# amplifier.net
KiCad netlist of a schematic drawn in Altium Designer
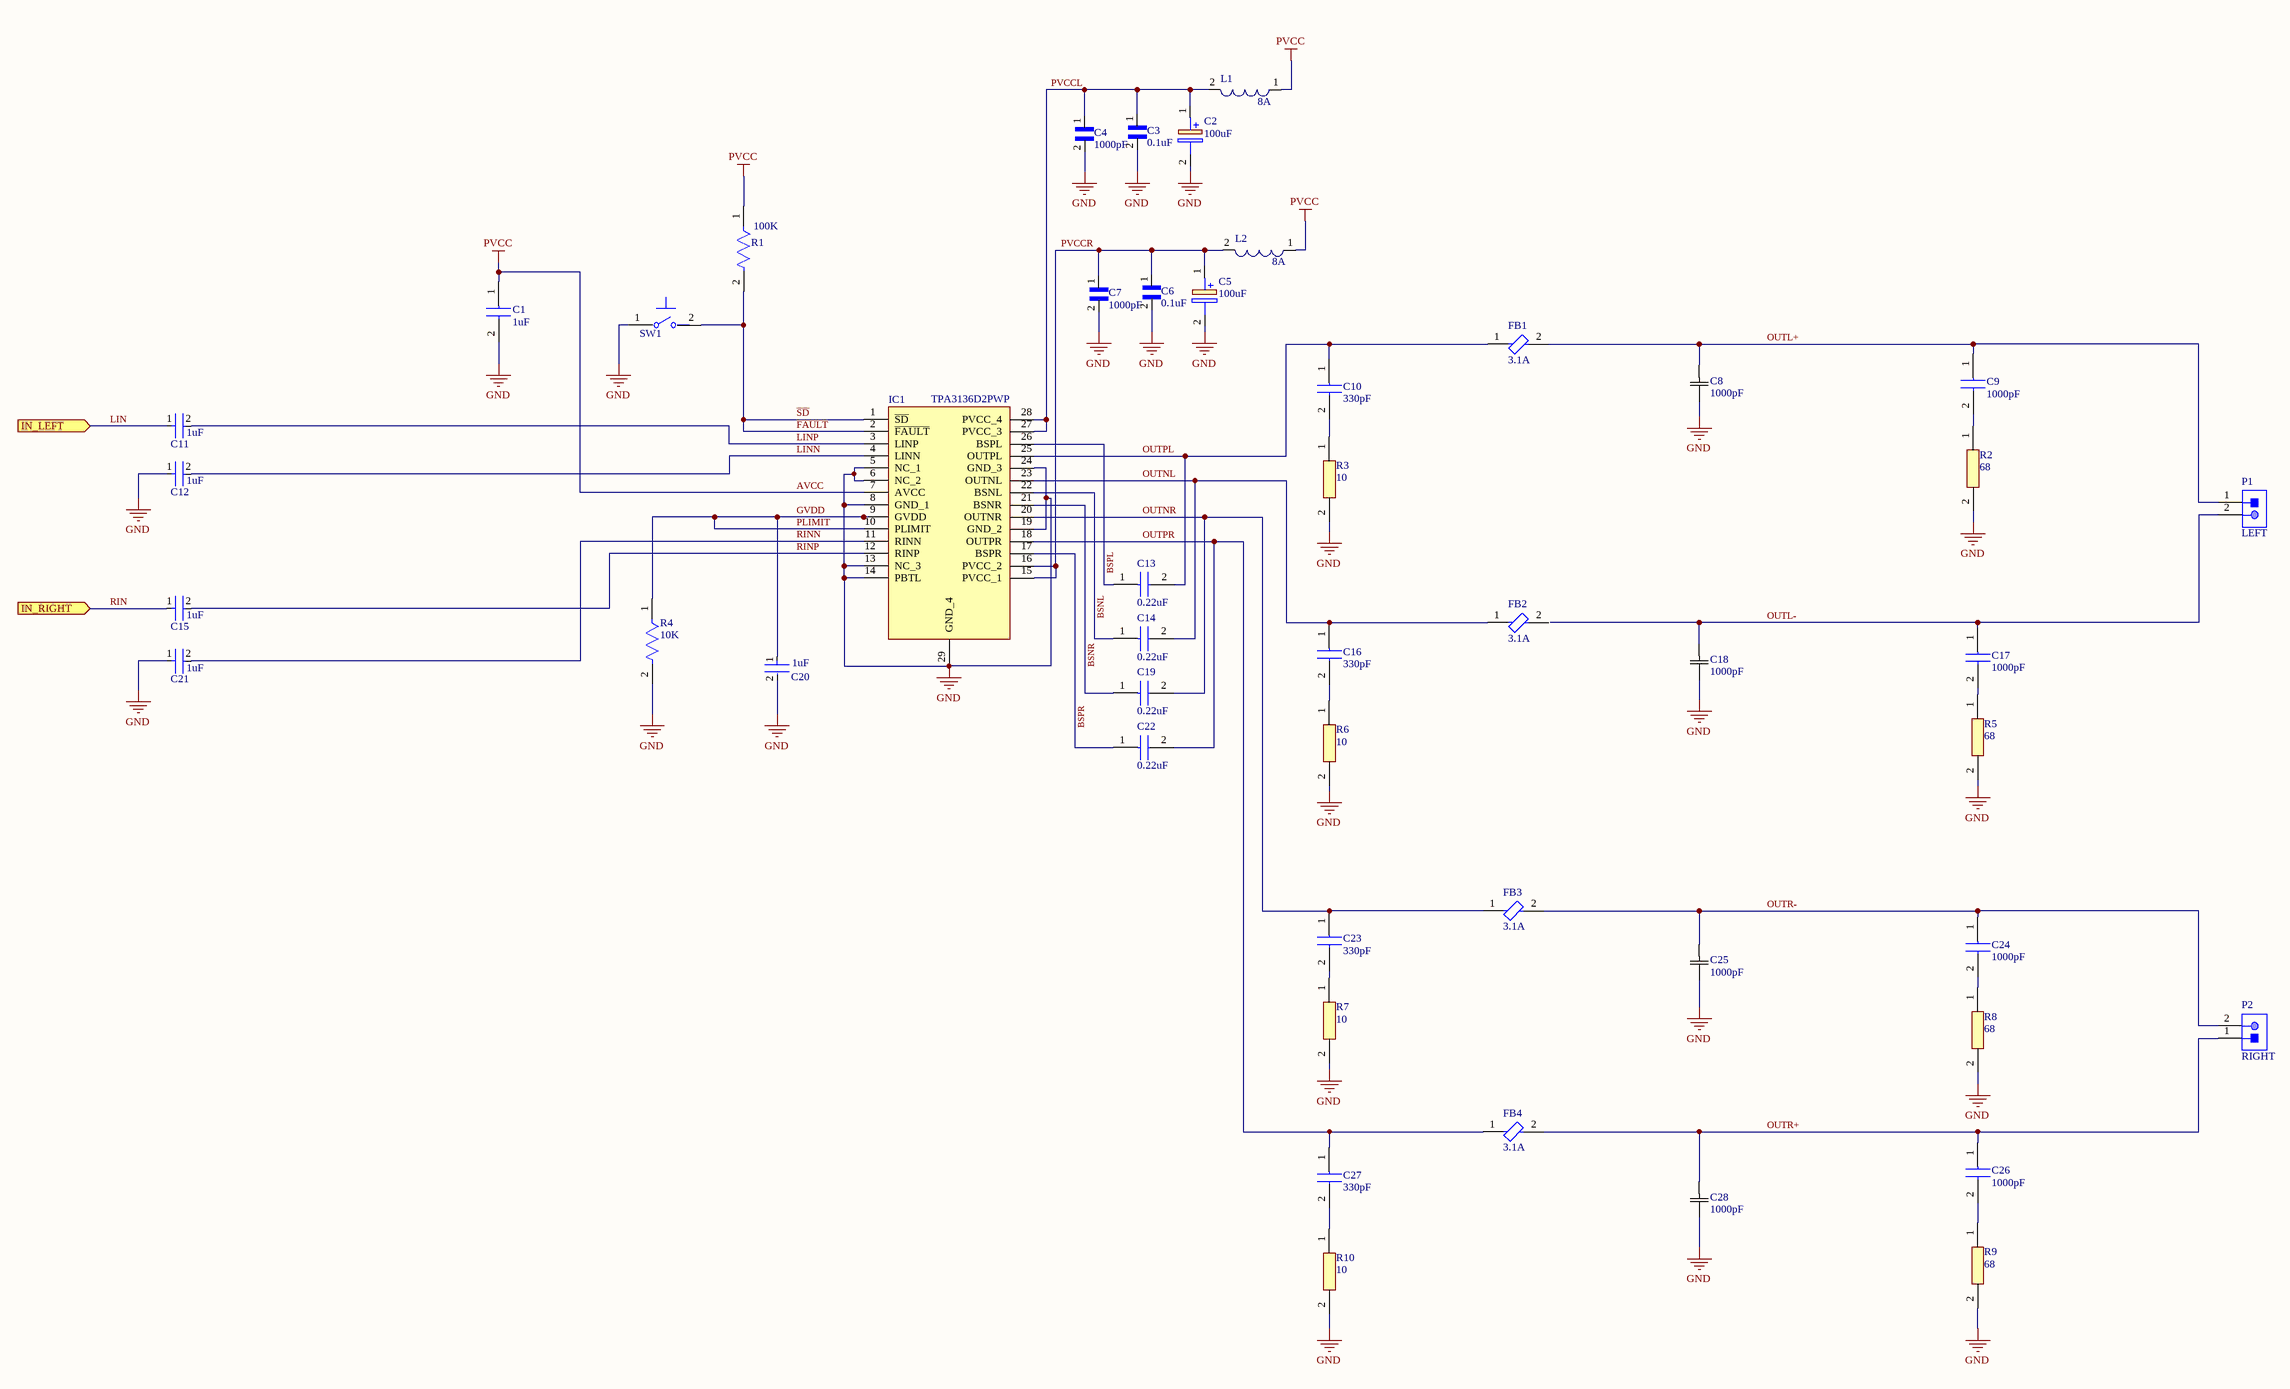
[diagram p0: amplifier.SchDoc]

(export (version "E")
  (design (tool "Eeschema 10.0.6"))
  (components
    (comp (ref "C1")
      (value "1uF")
      (footprint "CAPC1608X90N")
      (description "CAP CER 1UF 35V X5R 0603")
      (fields
        (field (name "MANUFACTURER_PART_NUMBER") "GMK107BJ105KA-T")
        (field (name "MOUSER PART NUMBER") "963-GMK107BJ105KA-T")
      )
      (libsource (lib "project_x_sch_library") (part "GMK107BJ105KA-T"))
    )
    (comp (ref "C2")
      (value "100uF")
      (footprint "CAPPRD350W60D825H1300")
      (description "CAP ALUM 100UF 20% 50V RADIAL")
      (fields
        (field (name "MANUFACTURER_PART_NUMBER") "UHE1H101MPD")
        (field (name "MOUSER PART NUMBER") "647-UHE1H101MPD")
      )
      (libsource (lib "project_x_sch_library") (part "UHE1H101MPD"))
    )
    (comp (ref "C3")
      (value "0.1uF")
      (footprint "CAPC1608X90N")
      (description "CAP CER 0.1UF 50V X7R 0603")
      (fields (field (name "MP") "CL10B104KB8NNNL") (field (name "MF") "Samsung Electro-Mechanics"))
      (libsource (lib "project_x_sch_library") (part "CL10B104KB8NNNL"))
    )
    (comp (ref "C4")
      (value "1000pF")
      (footprint "CAPC1608X90N")
      (description "1000pF ±5% 50V Ceramic Capacitor C0G, NP0 0603 (1608 Metric)")
      (fields (field (name "MP") "06035A102JAT2A"))
      (libsource (lib "project_x_sch_library") (part "06035A102JAT2A"))
    )
    (comp (ref "C5")
      (value "100uF")
      (footprint "CAPPRD350W60D825H1300")
      (description "CAP ALUM 100UF 20% 50V RADIAL")
      (fields
        (field (name "MANUFACTURER_PART_NUMBER") "UHE1H101MPD")
        (field (name "MOUSER PART NUMBER") "647-UHE1H101MPD")
      )
      (libsource (lib "project_x_sch_library") (part "UHE1H101MPD"))
    )
    (comp (ref "C6")
      (value "0.1uF")
      (footprint "CAPC1608X90N")
      (description "CAP CER 0.1UF 50V X7R 0603")
      (fields (field (name "MP") "CL10B104KB8NNNL") (field (name "MF") "Samsung Electro-Mechanics"))
      (libsource (lib "project_x_sch_library") (part "CL10B104KB8NNNL"))
    )
    (comp (ref "C7")
      (value "1000pF")
      (footprint "CAPC1608X90N")
      (description "1000pF ±5% 50V Ceramic Capacitor C0G, NP0 0603 (1608 Metric)")
      (fields (field (name "MP") "06035A102JAT2A"))
      (libsource (lib "project_x_sch_library") (part "06035A102JAT2A"))
    )
    (comp (ref "C8")
      (value "1000pF")
      (footprint "CAPC3216X94N")
      (description "CAP CER 1000PF 100V X7R 1206")
      (fields
        (field (name "MANUFACTURER_PART_NUMBER") "12061C102KAT2A")
        (field (name "COPYRIGHT") "Copyright (C) 2018 Accelerated Designs. All rights reserved")
      )
      (libsource (lib "project_x_sch_library") (part "12061C102KAT2A"))
    )
    (comp (ref "C9")
      (value "1000pF")
      (footprint "CAPC1608X90N")
      (description "CAP CER 1000PF 50V C0G/NP0 0603")
      (fields
        (field (name "MANUFACTURER_PART_NUMBER") "06035A102KAT2A")
        (field (name "MOUSER PART NUMBER") "581-06035A102KAT2A")
      )
      (libsource (lib "project_x_sch_library") (part "06035A102KAT2A"))
    )
    (comp (ref "C10")
      (value "330pF")
      (footprint "CAPC1608X90N")
      (description "CAP CER 330PF 50V C0G/NP0 0603")
      (fields
        (field (name "MANUFACTURER_PART_NUMBER") "06035A331JAT2A")
        (field (name "MOUSER PART NUMBER") "581-06035A331J")
      )
      (libsource (lib "project_x_sch_library") (part "06035A331JAT2A"))
    )
    (comp (ref "C11")
      (value "1uF")
      (footprint "TDK_CGA3E-0_3-0_1_IPC_A")
      (description "1µF ±10% 16V Ceramic Capacitor X7R 0603 (1608 Metric)")
      (libsource (lib "project_x_sch_library") (part "CGA3E1X7R1C105K080AC"))
    )
    (comp (ref "C12")
      (value "1uF")
      (footprint "TDK_CGA3E-0_3-0_1_IPC_A")
      (description "1µF ±10% 16V Ceramic Capacitor X7R 0603 (1608 Metric)")
      (libsource (lib "project_x_sch_library") (part "CGA3E1X7R1C105K080AC"))
    )
    (comp (ref "C13")
      (value "0.22uF")
      (footprint "CAPC1608X90N")
      (description "CAP CER 0.22UF 25V X5R 0603")
      (fields
        (field (name "MANUFACTURER_PART_NUMBER") "06033D224KAT2A")
        (field (name "MOUSER PART NUMBER") "581-06033D224K")
      )
      (libsource (lib "project_x_sch_library") (part "06033D224KAT2A"))
    )
    (comp (ref "C14")
      (value "0.22uF")
      (footprint "CAPC1608X90N")
      (description "CAP CER 0.22UF 25V X5R 0603")
      (fields
        (field (name "MANUFACTURER_PART_NUMBER") "06033D224KAT2A")
        (field (name "MOUSER PART NUMBER") "581-06033D224K")
      )
      (libsource (lib "project_x_sch_library") (part "06033D224KAT2A"))
    )
    (comp (ref "C15")
      (value "1uF")
      (footprint "TDK_CGA3E-0_3-0_1_IPC_A")
      (description "1µF ±10% 16V Ceramic Capacitor X7R 0603 (1608 Metric)")
      (libsource (lib "project_x_sch_library") (part "CGA3E1X7R1C105K080AC"))
    )
    (comp (ref "C16")
      (value "330pF")
      (footprint "CAPC1608X90N")
      (description "CAP CER 330PF 50V C0G/NP0 0603")
      (fields
        (field (name "MANUFACTURER_PART_NUMBER") "06035A331JAT2A")
        (field (name "MOUSER PART NUMBER") "581-06035A331J")
      )
      (libsource (lib "project_x_sch_library") (part "06035A331JAT2A"))
    )
    (comp (ref "C17")
      (value "1000pF")
      (footprint "CAPC1608X90N")
      (description "CAP CER 1000PF 50V C0G/NP0 0603")
      (fields
        (field (name "MANUFACTURER_PART_NUMBER") "06035A102KAT2A")
        (field (name "MOUSER PART NUMBER") "581-06035A102KAT2A")
      )
      (libsource (lib "project_x_sch_library") (part "06035A102KAT2A"))
    )
    (comp (ref "C18")
      (value "1000pF")
      (footprint "CAPC3216X94N")
      (description "CAP CER 1000PF 100V X7R 1206")
      (fields
        (field (name "MANUFACTURER_PART_NUMBER") "12061C102KAT2A")
        (field (name "COPYRIGHT") "Copyright (C) 2018 Accelerated Designs. All rights reserved")
      )
      (libsource (lib "project_x_sch_library") (part "12061C102KAT2A"))
    )
    (comp (ref "C19")
      (value "0.22uF")
      (footprint "CAPC1608X90N")
      (description "CAP CER 0.22UF 25V X5R 0603")
      (fields
        (field (name "MANUFACTURER_PART_NUMBER") "06033D224KAT2A")
        (field (name "MOUSER PART NUMBER") "581-06033D224K")
      )
      (libsource (lib "project_x_sch_library") (part "06033D224KAT2A"))
    )
    (comp (ref "C20")
      (value "1uF")
      (footprint "TDK_CGA3E-0_3-0_1_IPC_A")
      (description "1µF ±10% 16V Ceramic Capacitor X7R 0603 (1608 Metric)")
      (libsource (lib "project_x_sch_library") (part "CGA3E1X7R1C105K080AC"))
    )
    (comp (ref "C21")
      (value "1uF")
      (footprint "TDK_CGA3E-0_3-0_1_IPC_A")
      (description "1µF ±10% 16V Ceramic Capacitor X7R 0603 (1608 Metric)")
      (libsource (lib "project_x_sch_library") (part "CGA3E1X7R1C105K080AC"))
    )
    (comp (ref "C22")
      (value "0.22uF")
      (footprint "CAPC1608X90N")
      (description "CAP CER 0.22UF 25V X5R 0603")
      (fields
        (field (name "MANUFACTURER_PART_NUMBER") "06033D224KAT2A")
        (field (name "MOUSER PART NUMBER") "581-06033D224K")
      )
      (libsource (lib "project_x_sch_library") (part "06033D224KAT2A"))
    )
    (comp (ref "C23")
      (value "330pF")
      (footprint "CAPC1608X90N")
      (description "CAP CER 330PF 50V C0G/NP0 0603")
      (fields
        (field (name "MANUFACTURER_PART_NUMBER") "06035A331JAT2A")
        (field (name "MOUSER PART NUMBER") "581-06035A331J")
      )
      (libsource (lib "project_x_sch_library") (part "06035A331JAT2A"))
    )
    (comp (ref "C24")
      (value "1000pF")
      (footprint "CAPC1608X90N")
      (description "CAP CER 1000PF 50V C0G/NP0 0603")
      (fields
        (field (name "MANUFACTURER_PART_NUMBER") "06035A102KAT2A")
        (field (name "MOUSER PART NUMBER") "581-06035A102KAT2A")
      )
      (libsource (lib "project_x_sch_library") (part "06035A102KAT2A"))
    )
    (comp (ref "C25")
      (value "1000pF")
      (footprint "CAPC3216X94N")
      (description "CAP CER 1000PF 100V X7R 1206")
      (fields
        (field (name "MANUFACTURER_PART_NUMBER") "12061C102KAT2A")
        (field (name "COPYRIGHT") "Copyright (C) 2018 Accelerated Designs. All rights reserved")
      )
      (libsource (lib "project_x_sch_library") (part "12061C102KAT2A"))
    )
    (comp (ref "C26")
      (value "1000pF")
      (footprint "CAPC1608X90N")
      (description "CAP CER 1000PF 50V C0G/NP0 0603")
      (fields
        (field (name "MANUFACTURER_PART_NUMBER") "06035A102KAT2A")
        (field (name "MOUSER PART NUMBER") "581-06035A102KAT2A")
      )
      (libsource (lib "project_x_sch_library") (part "06035A102KAT2A"))
    )
    (comp (ref "C27")
      (value "330pF")
      (footprint "CAPC1608X90N")
      (description "CAP CER 330PF 50V C0G/NP0 0603")
      (fields
        (field (name "MANUFACTURER_PART_NUMBER") "06035A331JAT2A")
        (field (name "MOUSER PART NUMBER") "581-06035A331J")
      )
      (libsource (lib "project_x_sch_library") (part "06035A331JAT2A"))
    )
    (comp (ref "C28")
      (value "1000pF")
      (footprint "CAPC3216X94N")
      (description "CAP CER 1000PF 100V X7R 1206")
      (fields
        (field (name "MANUFACTURER_PART_NUMBER") "12061C102KAT2A")
        (field (name "COPYRIGHT") "Copyright (C) 2018 Accelerated Designs. All rights reserved")
      )
      (libsource (lib "project_x_sch_library") (part "12061C102KAT2A"))
    )
    (comp (ref "FB1")
      (value "3.1A")
      (footprint "Murata_NFZ2MSD-d5_IPC_A")
      (description "300 Ohms @ 100MHz 1  Ferrite Bead 0806 (2016 Metric) 3.8A 26mOhm")
      (libsource (lib "project_x_sch_library") (part "NFZ2MSD301SZ10L"))
    )
    (comp (ref "FB2")
      (value "3.1A")
      (footprint "Murata_NFZ2MSD-d5_IPC_A")
      (description "300 Ohms @ 100MHz 1  Ferrite Bead 0806 (2016 Metric) 3.8A 26mOhm")
      (libsource (lib "project_x_sch_library") (part "NFZ2MSD301SZ10L"))
    )
    (comp (ref "FB3")
      (value "3.1A")
      (footprint "Murata_NFZ2MSD-d5_IPC_A")
      (description "300 Ohms @ 100MHz 1  Ferrite Bead 0806 (2016 Metric) 3.8A 26mOhm")
      (libsource (lib "project_x_sch_library") (part "NFZ2MSD301SZ10L"))
    )
    (comp (ref "FB4")
      (value "3.1A")
      (footprint "Murata_NFZ2MSD-d5_IPC_A")
      (description "300 Ohms @ 100MHz 1  Ferrite Bead 0806 (2016 Metric) 3.8A 26mOhm")
      (libsource (lib "project_x_sch_library") (part "NFZ2MSD301SZ10L"))
    )
    (comp (ref "IC1")
      (value "TPA3136D2PWP")
      (footprint "SOP65P640X120-29N")
      (description "IC AMP CLASS D STER 10W 28HTSSOP")
      (fields (field (name "MOUSER PART NUMBER") "595-TPA3136D2PWP"))
      (libsource (lib "project_x_sch_library") (part "TPA3136D2PWP"))
    )
    (comp (ref "L1")
      (value "8A")
      (footprint "WE-MPSB-1812")
      (description "100 Ohms @ 100MHz 1  Ferrite Bead 1812 (4532 Metric) 8A 6mOhm")
      (fields (field (name "PARTNUMBER") "74279226101") (field (name "MANUFACTURER") "Wuerth Elektronik"))
      (libsource (lib "project_x_sch_library") (part "74279226101"))
    )
    (comp (ref "L2")
      (value "8A")
      (footprint "WE-MPSB-1812")
      (description "100 Ohms @ 100MHz 1  Ferrite Bead 1812 (4532 Metric) 8A 6mOhm")
      (fields (field (name "PARTNUMBER") "74279226101") (field (name "MANUFACTURER") "Wuerth Elektronik"))
      (libsource (lib "project_x_sch_library") (part "74279226101"))
    )
    (comp (ref "P1")
      (value "LEFT")
      (footprint "PHOE-1803277_V")
      (fields (field (name "TOLERANCE") "5%") (field (name "PARTNUMBER") "1803277"))
      (libsource (lib "") (part "1803277_1"))
    )
    (comp (ref "P2")
      (value "RIGHT")
      (footprint "PHOE-1803277_V")
      (fields (field (name "TOLERANCE") "5%") (field (name "PARTNUMBER") "1803277"))
      (libsource (lib "project_x_sch_library") (part "1803277"))
    )
    (comp (ref "R1")
      (value "100K")
      (footprint "TE_Connectivity_CPF0603_IPC_A")
      (description "100 kOhms ±1% 0.063W, 1/16W Chip Resistor 0603 (1608 Metric)  Thin Film")
      (libsource (lib "project_x_sch_library") (part "CPF0603F100KC1"))
    )
    (comp (ref "R2")
      (value "68")
      (footprint "RESC1608X55N - duplicate")
      (description "RES SMD 68 OHM 5% 1/10W 0603")
      (fields
        (field (name "MANUFACTURER_PART_NUMBER") "RC0603JR-0768RL")
        (field (name "MOUSER PART NUMBER") "603-RC0603JR-0768RL")
      )
      (libsource (lib "project_x_sch_library") (part "RC0603JR-0768RL"))
    )
    (comp (ref "R3")
      (value "10")
      (footprint "RESC1608X55N")
      (description "RES SMD 10 OHM 1% 1/4W 0603")
      (fields
        (field (name "MANUFACTURER_PART_NUMBER") "ESR03EZPF10R0")
        (field (name "MOUSER PART NUMBER") "755-ESR03EZPF10R0")
      )
      (libsource (lib "project_x_sch_library") (part "ESR03EZPF10R0"))
    )
    (comp (ref "R4")
      (value "10K")
      (footprint "Yageo_RT0603_IPC_A")
      (description "RES SMD 10K OHM 0.1% 1/10W 0603")
      (libsource (lib "project_x_sch_library") (part "RT0603BRB0710KL"))
    )
    (comp (ref "R5")
      (value "68")
      (footprint "RESC1608X55N - duplicate")
      (description "RES SMD 68 OHM 5% 1/10W 0603")
      (fields
        (field (name "MANUFACTURER_PART_NUMBER") "RC0603JR-0768RL")
        (field (name "MOUSER PART NUMBER") "603-RC0603JR-0768RL")
      )
      (libsource (lib "project_x_sch_library") (part "RC0603JR-0768RL"))
    )
    (comp (ref "R6")
      (value "10")
      (footprint "RESC1608X55N")
      (description "RES SMD 10 OHM 1% 1/4W 0603")
      (fields
        (field (name "MANUFACTURER_PART_NUMBER") "ESR03EZPF10R0")
        (field (name "MOUSER PART NUMBER") "755-ESR03EZPF10R0")
      )
      (libsource (lib "project_x_sch_library") (part "ESR03EZPF10R0"))
    )
    (comp (ref "R7")
      (value "10")
      (footprint "RESC1608X55N")
      (description "RES SMD 10 OHM 1% 1/4W 0603")
      (fields
        (field (name "MANUFACTURER_PART_NUMBER") "ESR03EZPF10R0")
        (field (name "MOUSER PART NUMBER") "755-ESR03EZPF10R0")
      )
      (libsource (lib "project_x_sch_library") (part "ESR03EZPF10R0"))
    )
    (comp (ref "R8")
      (value "68")
      (footprint "RESC1608X55N - duplicate")
      (description "RES SMD 68 OHM 5% 1/10W 0603")
      (fields
        (field (name "MANUFACTURER_PART_NUMBER") "RC0603JR-0768RL")
        (field (name "MOUSER PART NUMBER") "603-RC0603JR-0768RL")
      )
      (libsource (lib "project_x_sch_library") (part "RC0603JR-0768RL"))
    )
    (comp (ref "R9")
      (value "68")
      (footprint "RESC1608X55N - duplicate")
      (description "RES SMD 68 OHM 5% 1/10W 0603")
      (fields
        (field (name "MANUFACTURER_PART_NUMBER") "RC0603JR-0768RL")
        (field (name "MOUSER PART NUMBER") "603-RC0603JR-0768RL")
      )
      (libsource (lib "project_x_sch_library") (part "RC0603JR-0768RL"))
    )
    (comp (ref "R10")
      (value "10")
      (footprint "RESC1608X55N")
      (description "RES SMD 10 OHM 1% 1/4W 0603")
      (fields
        (field (name "MANUFACTURER_PART_NUMBER") "ESR03EZPF10R0")
        (field (name "MOUSER PART NUMBER") "755-ESR03EZPF10R0")
      )
      (libsource (lib "project_x_sch_library") (part "ESR03EZPF10R0"))
    )
    (comp (ref "SW1")
      (value "TL1015AF160QG")
      (footprint "E-Switch_0_MFG")
      (description "SWITCH TACTILE SPST-NO 0.05A 12V")
      (libsource (lib "project_x_sch_library") (part "TL1015AF160QG"))
    )
  )
  (nets
    (net (code "1") (name "/BSNL") (class "Default")
      (node (ref "C14") (pin "1") (pinfunction "1_1") (pintype "passive"))
      (node (ref "IC1") (pin "22") (pinfunction "BSNL_22") (pintype "passive"))
    )
    (net (code "2") (name "/BSNR") (class "Default")
      (node (ref "C19") (pin "1") (pinfunction "1_1") (pintype "passive"))
      (node (ref "IC1") (pin "21") (pinfunction "BSNR_21") (pintype "passive"))
    )
    (net (code "3") (name "/BSPL") (class "Default")
      (node (ref "C13") (pin "1") (pinfunction "1_1") (pintype "passive"))
      (node (ref "IC1") (pin "26") (pinfunction "BSPL_26") (pintype "passive"))
    )
    (net (code "4") (name "/BSPR") (class "Default")
      (node (ref "C22") (pin "1") (pinfunction "1_1") (pintype "passive"))
      (node (ref "IC1") (pin "17") (pinfunction "BSPR_17") (pintype "passive"))
    )
    (net (code "5") (name "/GVDD") (class "Default")
      (node (ref "C20") (pin "1") (pinfunction "1_1") (pintype "passive"))
      (node (ref "IC1") (pin "10") (pinfunction "PLIMIT_10") (pintype "passive"))
      (node (ref "IC1") (pin "9") (pinfunction "GVDD_9") (pintype "passive"))
      (node (ref "R4") (pin "1") (pinfunction "1_1") (pintype "passive"))
    )
    (net (code "6") (name "/LIN") (class "Default")
      (node (ref "C11") (pin "1") (pinfunction "1_1") (pintype "passive"))
    )
    (net (code "7") (name "/LINN") (class "Default")
      (node (ref "C12") (pin "2") (pinfunction "2_2") (pintype "passive"))
      (node (ref "IC1") (pin "4") (pinfunction "LINN_4") (pintype "passive"))
    )
    (net (code "8") (name "/LINP") (class "Default")
      (node (ref "C11") (pin "2") (pinfunction "2_2") (pintype "passive"))
      (node (ref "IC1") (pin "3") (pinfunction "LINP_3") (pintype "passive"))
    )
    (net (code "9") (name "/OUTL+") (class "Default")
      (node (ref "C8") (pin "1") (pinfunction "11_1") (pintype "passive"))
      (node (ref "C9") (pin "1") (pinfunction "1_1") (pintype "passive"))
      (node (ref "FB1") (pin "2") (pinfunction "2_2") (pintype "passive"))
      (node (ref "P1") (pin "1") (pinfunction "1_1") (pintype "passive"))
    )
    (net (code "10") (name "/OUTL-") (class "Default")
      (node (ref "C17") (pin "1") (pinfunction "1_1") (pintype "passive"))
      (node (ref "C18") (pin "1") (pinfunction "11_1") (pintype "passive"))
      (node (ref "P1") (pin "2") (pinfunction "2_2") (pintype "passive"))
    )
    (net (code "11") (name "/OUTNL") (class "Default")
      (node (ref "C14") (pin "2") (pinfunction "2_2") (pintype "passive"))
      (node (ref "C16") (pin "1") (pinfunction "1_1") (pintype "passive"))
      (node (ref "FB2") (pin "1") (pinfunction "1_1") (pintype "passive"))
      (node (ref "IC1") (pin "23") (pinfunction "OUTNL_23") (pintype "passive"))
    )
    (net (code "12") (name "/OUTNR") (class "Default")
      (node (ref "C19") (pin "2") (pinfunction "2_2") (pintype "passive"))
      (node (ref "C23") (pin "1") (pinfunction "1_1") (pintype "passive"))
      (node (ref "FB3") (pin "1") (pinfunction "1_1") (pintype "passive"))
      (node (ref "IC1") (pin "20") (pinfunction "OUTNR_20") (pintype "passive"))
    )
    (net (code "13") (name "/OUTPL") (class "Default")
      (node (ref "C10") (pin "1") (pinfunction "1_1") (pintype "passive"))
      (node (ref "C13") (pin "2") (pinfunction "2_2") (pintype "passive"))
      (node (ref "FB1") (pin "1") (pinfunction "1_1") (pintype "passive"))
      (node (ref "IC1") (pin "25") (pinfunction "OUTPL_25") (pintype "passive"))
    )
    (net (code "14") (name "/OUTPR") (class "Default")
      (node (ref "C22") (pin "2") (pinfunction "2_2") (pintype "passive"))
      (node (ref "C27") (pin "1") (pinfunction "1_1") (pintype "passive"))
      (node (ref "FB4") (pin "1") (pinfunction "1_1") (pintype "passive"))
      (node (ref "IC1") (pin "18") (pinfunction "OUTPR_18") (pintype "passive"))
    )
    (net (code "15") (name "/OUTR+") (class "Default")
      (node (ref "C26") (pin "1") (pinfunction "1_1") (pintype "passive"))
      (node (ref "C28") (pin "1") (pinfunction "11_1") (pintype "passive"))
      (node (ref "FB4") (pin "2") (pinfunction "2_2") (pintype "passive"))
      (node (ref "P2") (pin "1") (pinfunction "1_1") (pintype "passive"))
    )
    (net (code "16") (name "/OUTR-") (class "Default")
      (node (ref "C24") (pin "1") (pinfunction "1_1") (pintype "passive"))
      (node (ref "C25") (pin "1") (pinfunction "11_1") (pintype "passive"))
      (node (ref "FB3") (pin "2") (pinfunction "2_2") (pintype "passive"))
      (node (ref "P2") (pin "2") (pinfunction "2_2") (pintype "passive"))
    )
    (net (code "17") (name "/PVCCL") (class "Default")
      (node (ref "C2") (pin "1") (pinfunction "+_1") (pintype "passive"))
      (node (ref "C3") (pin "1") (pinfunction "1_1") (pintype "passive"))
      (node (ref "C4") (pin "1") (pinfunction "1_1") (pintype "passive"))
      (node (ref "IC1") (pin "27") (pinfunction "PVCC_3_27") (pintype "passive"))
      (node (ref "IC1") (pin "28") (pinfunction "PVCC_4_28") (pintype "passive"))
      (node (ref "L1") (pin "2") (pinfunction "2_2") (pintype "passive"))
    )
    (net (code "18") (name "/PVCCR") (class "Default")
      (node (ref "C5") (pin "1") (pinfunction "+_1") (pintype "passive"))
      (node (ref "C6") (pin "1") (pinfunction "1_1") (pintype "passive"))
      (node (ref "C7") (pin "1") (pinfunction "1_1") (pintype "passive"))
      (node (ref "IC1") (pin "15") (pinfunction "PVCC_1_15") (pintype "passive"))
      (node (ref "IC1") (pin "16") (pinfunction "PVCC_2_16") (pintype "passive"))
      (node (ref "L2") (pin "2") (pinfunction "2_2") (pintype "passive"))
    )
    (net (code "19") (name "/RIN") (class "Default")
      (node (ref "C15") (pin "1") (pinfunction "1_1") (pintype "passive"))
    )
    (net (code "21") (name "/RINN") (class "Default")
      (node (ref "C21") (pin "2") (pinfunction "2_2") (pintype "passive"))
      (node (ref "IC1") (pin "11") (pinfunction "RINN_11") (pintype "passive"))
    )
    (net (code "22") (name "/RINP") (class "Default")
      (node (ref "C15") (pin "2") (pinfunction "2_2") (pintype "passive"))
      (node (ref "IC1") (pin "12") (pinfunction "RINP_12") (pintype "passive"))
    )
    (net (code "23") (name "/~{FAULT}") (class "Default")
      (node (ref "IC1") (pin "1") (pinfunction "~{SD}_1") (pintype "passive"))
      (node (ref "IC1") (pin "2") (pinfunction "~{FAULT}_2") (pintype "passive"))
      (node (ref "R1") (pin "2") (pinfunction "2_2") (pintype "passive"))
      (node (ref "SW1") (pin "2") (pinfunction "2_2") (pintype "passive"))
    )
    (net (code "24") (name "GND") (class "Default")
      (node (ref "C1") (pin "2") (pinfunction "2_2") (pintype "passive"))
      (node (ref "C12") (pin "1") (pinfunction "1_1") (pintype "passive"))
      (node (ref "C18") (pin "2") (pinfunction "12_2") (pintype "passive"))
      (node (ref "C2") (pin "2") (pinfunction "-_2") (pintype "passive"))
      (node (ref "C20") (pin "2") (pinfunction "2_2") (pintype "passive"))
      (node (ref "C21") (pin "1") (pinfunction "1_1") (pintype "passive"))
      (node (ref "C25") (pin "2") (pinfunction "12_2") (pintype "passive"))
      (node (ref "C28") (pin "2") (pinfunction "12_2") (pintype "passive"))
      (node (ref "C3") (pin "2") (pinfunction "2_2") (pintype "passive"))
      (node (ref "C4") (pin "2") (pinfunction "2_2") (pintype "passive"))
      (node (ref "C5") (pin "2") (pinfunction "-_2") (pintype "passive"))
      (node (ref "C6") (pin "2") (pinfunction "2_2") (pintype "passive"))
      (node (ref "C7") (pin "2") (pinfunction "2_2") (pintype "passive"))
      (node (ref "C8") (pin "2") (pinfunction "12_2") (pintype "passive"))
      (node (ref "IC1") (pin "13") (pinfunction "NC_3_13") (pintype "passive"))
      (node (ref "IC1") (pin "14") (pinfunction "PBTL_14") (pintype "passive"))
      (node (ref "IC1") (pin "19") (pinfunction "GND_2_19") (pintype "passive"))
      (node (ref "IC1") (pin "24") (pinfunction "GND_3_24") (pintype "passive"))
      (node (ref "IC1") (pin "29") (pinfunction "GND_4_29") (pintype "passive"))
      (node (ref "IC1") (pin "5") (pinfunction "NC_1_5") (pintype "passive"))
      (node (ref "IC1") (pin "6") (pinfunction "NC_2_6") (pintype "passive"))
      (node (ref "IC1") (pin "8") (pinfunction "GND_1_8") (pintype "passive"))
      (node (ref "R10") (pin "2") (pinfunction "2_2") (pintype "passive"))
      (node (ref "R2") (pin "2") (pinfunction "2_2") (pintype "passive"))
      (node (ref "R3") (pin "2") (pinfunction "2_2") (pintype "passive"))
      (node (ref "R4") (pin "2") (pinfunction "2_2") (pintype "passive"))
      (node (ref "R5") (pin "2") (pinfunction "2_2") (pintype "passive"))
      (node (ref "R6") (pin "2") (pinfunction "2_2") (pintype "passive"))
      (node (ref "R7") (pin "2") (pinfunction "2_2") (pintype "passive"))
      (node (ref "R8") (pin "2") (pinfunction "2_2") (pintype "passive"))
      (node (ref "R9") (pin "2") (pinfunction "2_2") (pintype "passive"))
      (node (ref "SW1") (pin "1") (pinfunction "1_1") (pintype "passive"))
    )
    (net (code "25") (name "Net-(C9-Pad2)") (class "Default")
      (node (ref "C9") (pin "2") (pinfunction "2_2") (pintype "passive"))
      (node (ref "R2") (pin "1") (pinfunction "1_1") (pintype "passive"))
    )
    (net (code "26") (name "Net-(C10-Pad2)") (class "Default")
      (node (ref "C10") (pin "2") (pinfunction "2_2") (pintype "passive"))
      (node (ref "R3") (pin "1") (pinfunction "1_1") (pintype "passive"))
    )
    (net (code "27") (name "Net-(C16-Pad2)") (class "Default")
      (node (ref "C16") (pin "2") (pinfunction "2_2") (pintype "passive"))
      (node (ref "R6") (pin "1") (pinfunction "1_1") (pintype "passive"))
    )
    (net (code "28") (name "Net-(C17-Pad2)") (class "Default")
      (node (ref "C17") (pin "2") (pinfunction "2_2") (pintype "passive"))
      (node (ref "R5") (pin "1") (pinfunction "1_1") (pintype "passive"))
    )
    (net (code "29") (name "Net-(C23-Pad2)") (class "Default")
      (node (ref "C23") (pin "2") (pinfunction "2_2") (pintype "passive"))
      (node (ref "R7") (pin "1") (pinfunction "1_1") (pintype "passive"))
    )
    (net (code "30") (name "Net-(C24-Pad2)") (class "Default")
      (node (ref "C24") (pin "2") (pinfunction "2_2") (pintype "passive"))
      (node (ref "R8") (pin "1") (pinfunction "1_1") (pintype "passive"))
    )
    (net (code "31") (name "Net-(C26-Pad2)") (class "Default")
      (node (ref "C26") (pin "2") (pinfunction "2_2") (pintype "passive"))
      (node (ref "R9") (pin "1") (pinfunction "1_1") (pintype "passive"))
    )
    (net (code "32") (name "Net-(C27-Pad2)") (class "Default")
      (node (ref "C27") (pin "2") (pinfunction "2_2") (pintype "passive"))
      (node (ref "R10") (pin "1") (pinfunction "1_1") (pintype "passive"))
    )
    (net (code "33") (name "PVCC") (class "Default")
      (node (ref "C1") (pin "1") (pinfunction "1_1") (pintype "passive"))
      (node (ref "IC1") (pin "7") (pinfunction "AVCC_7") (pintype "passive"))
      (node (ref "L1") (pin "1") (pinfunction "1_1") (pintype "passive"))
      (node (ref "L2") (pin "1") (pinfunction "1_1") (pintype "passive"))
      (node (ref "R1") (pin "1") (pinfunction "1_1") (pintype "passive"))
    )
    (net (code "34") (name "unconnected-(FB2-Pad2)") (class "Default")
      (node (ref "FB2") (pin "2") (pinfunction "2_2") (pintype "passive"))
    )
  )
)
